# axiom_beta_interface_dummy_v0_8_540d2087.net
KiCad netlist of a schematic drawn in EAGLE
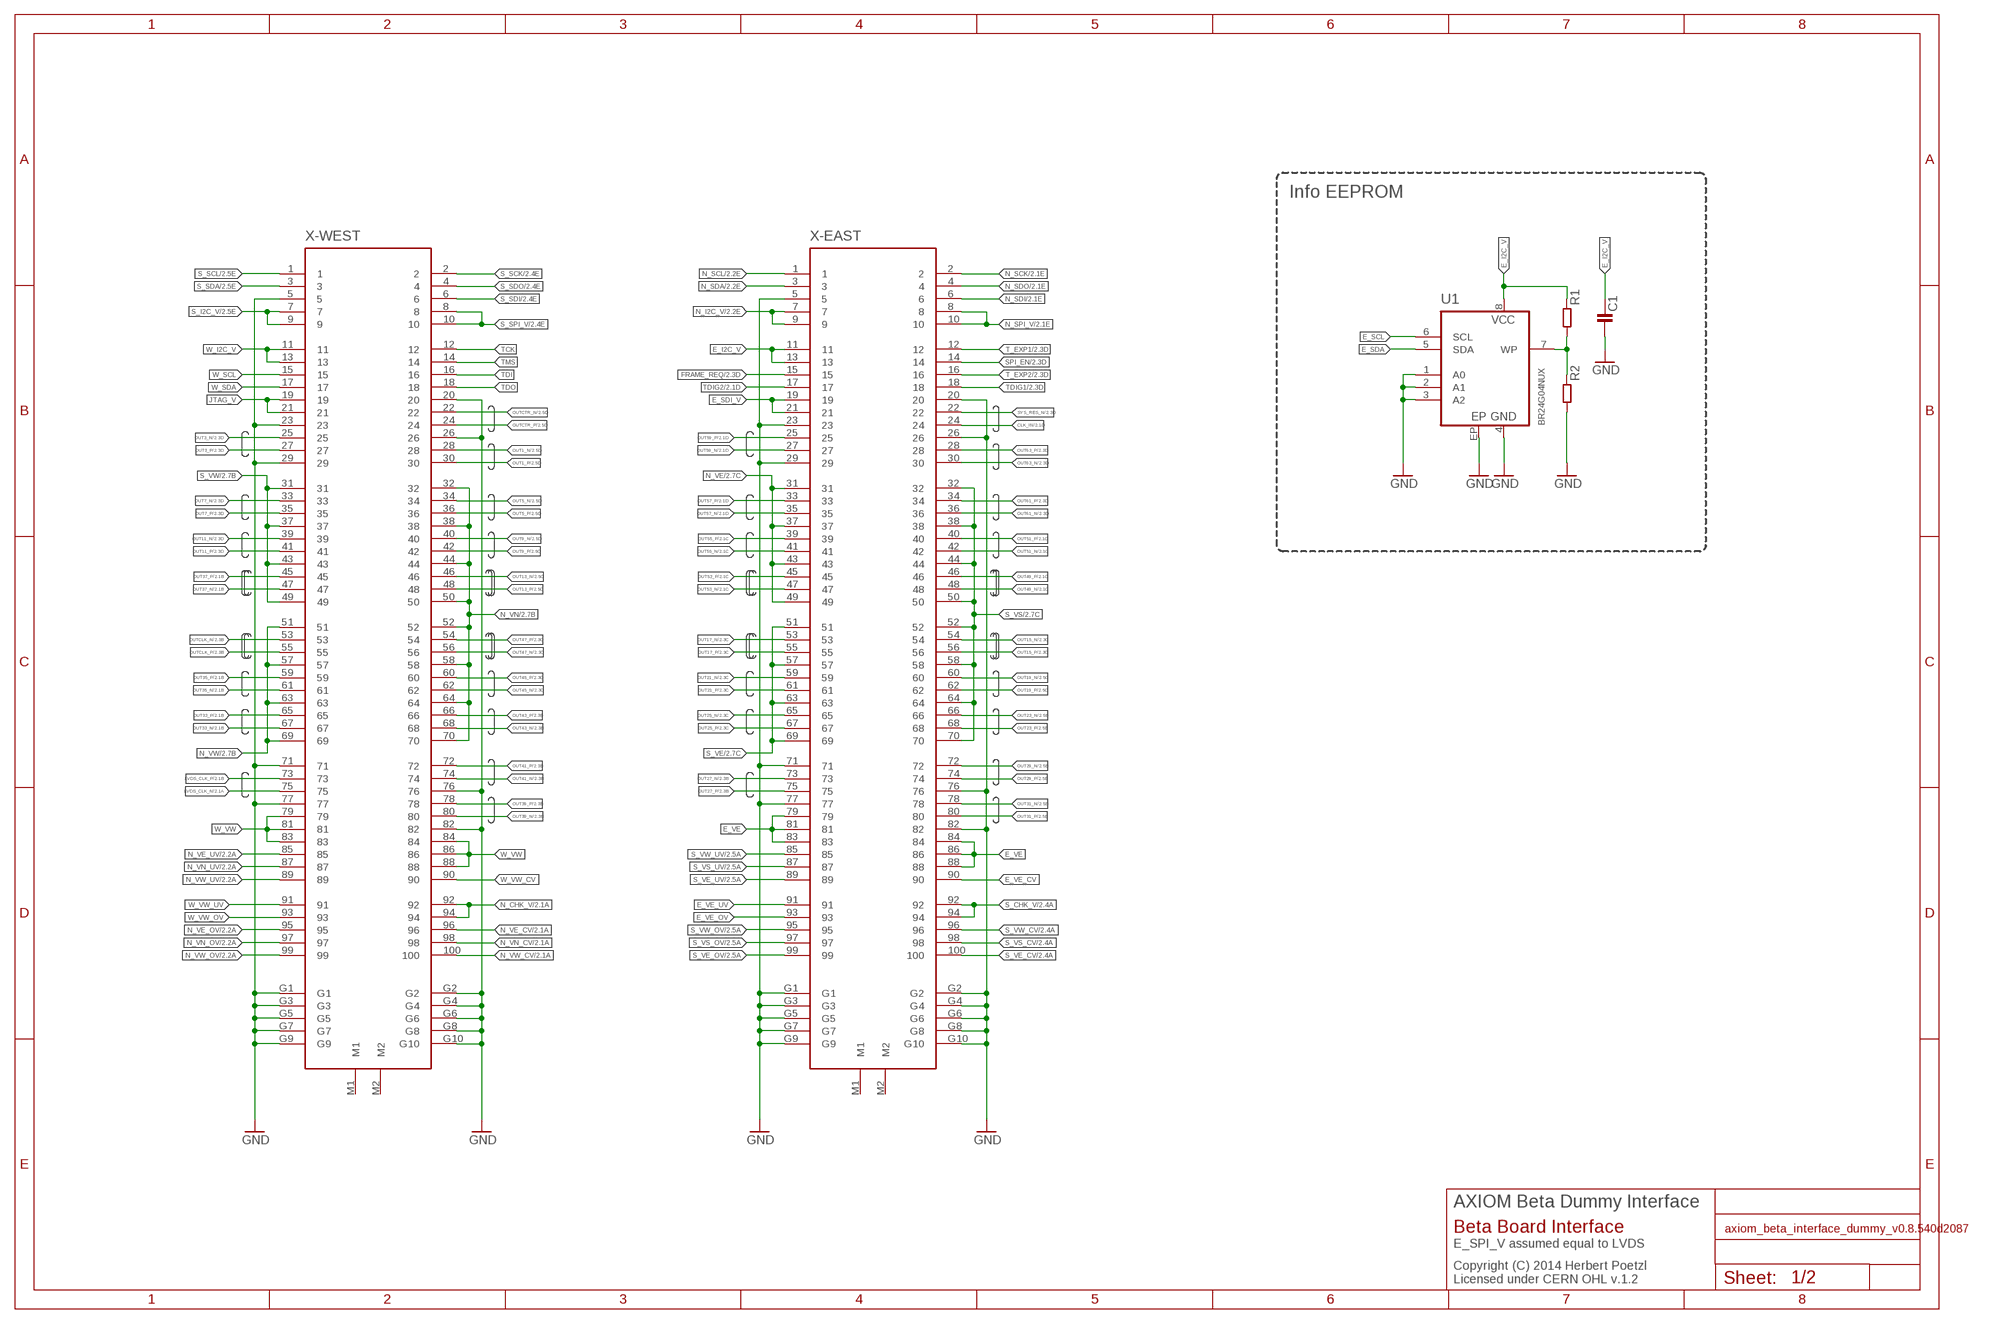
[diagram p0: schematic, sheet 1]
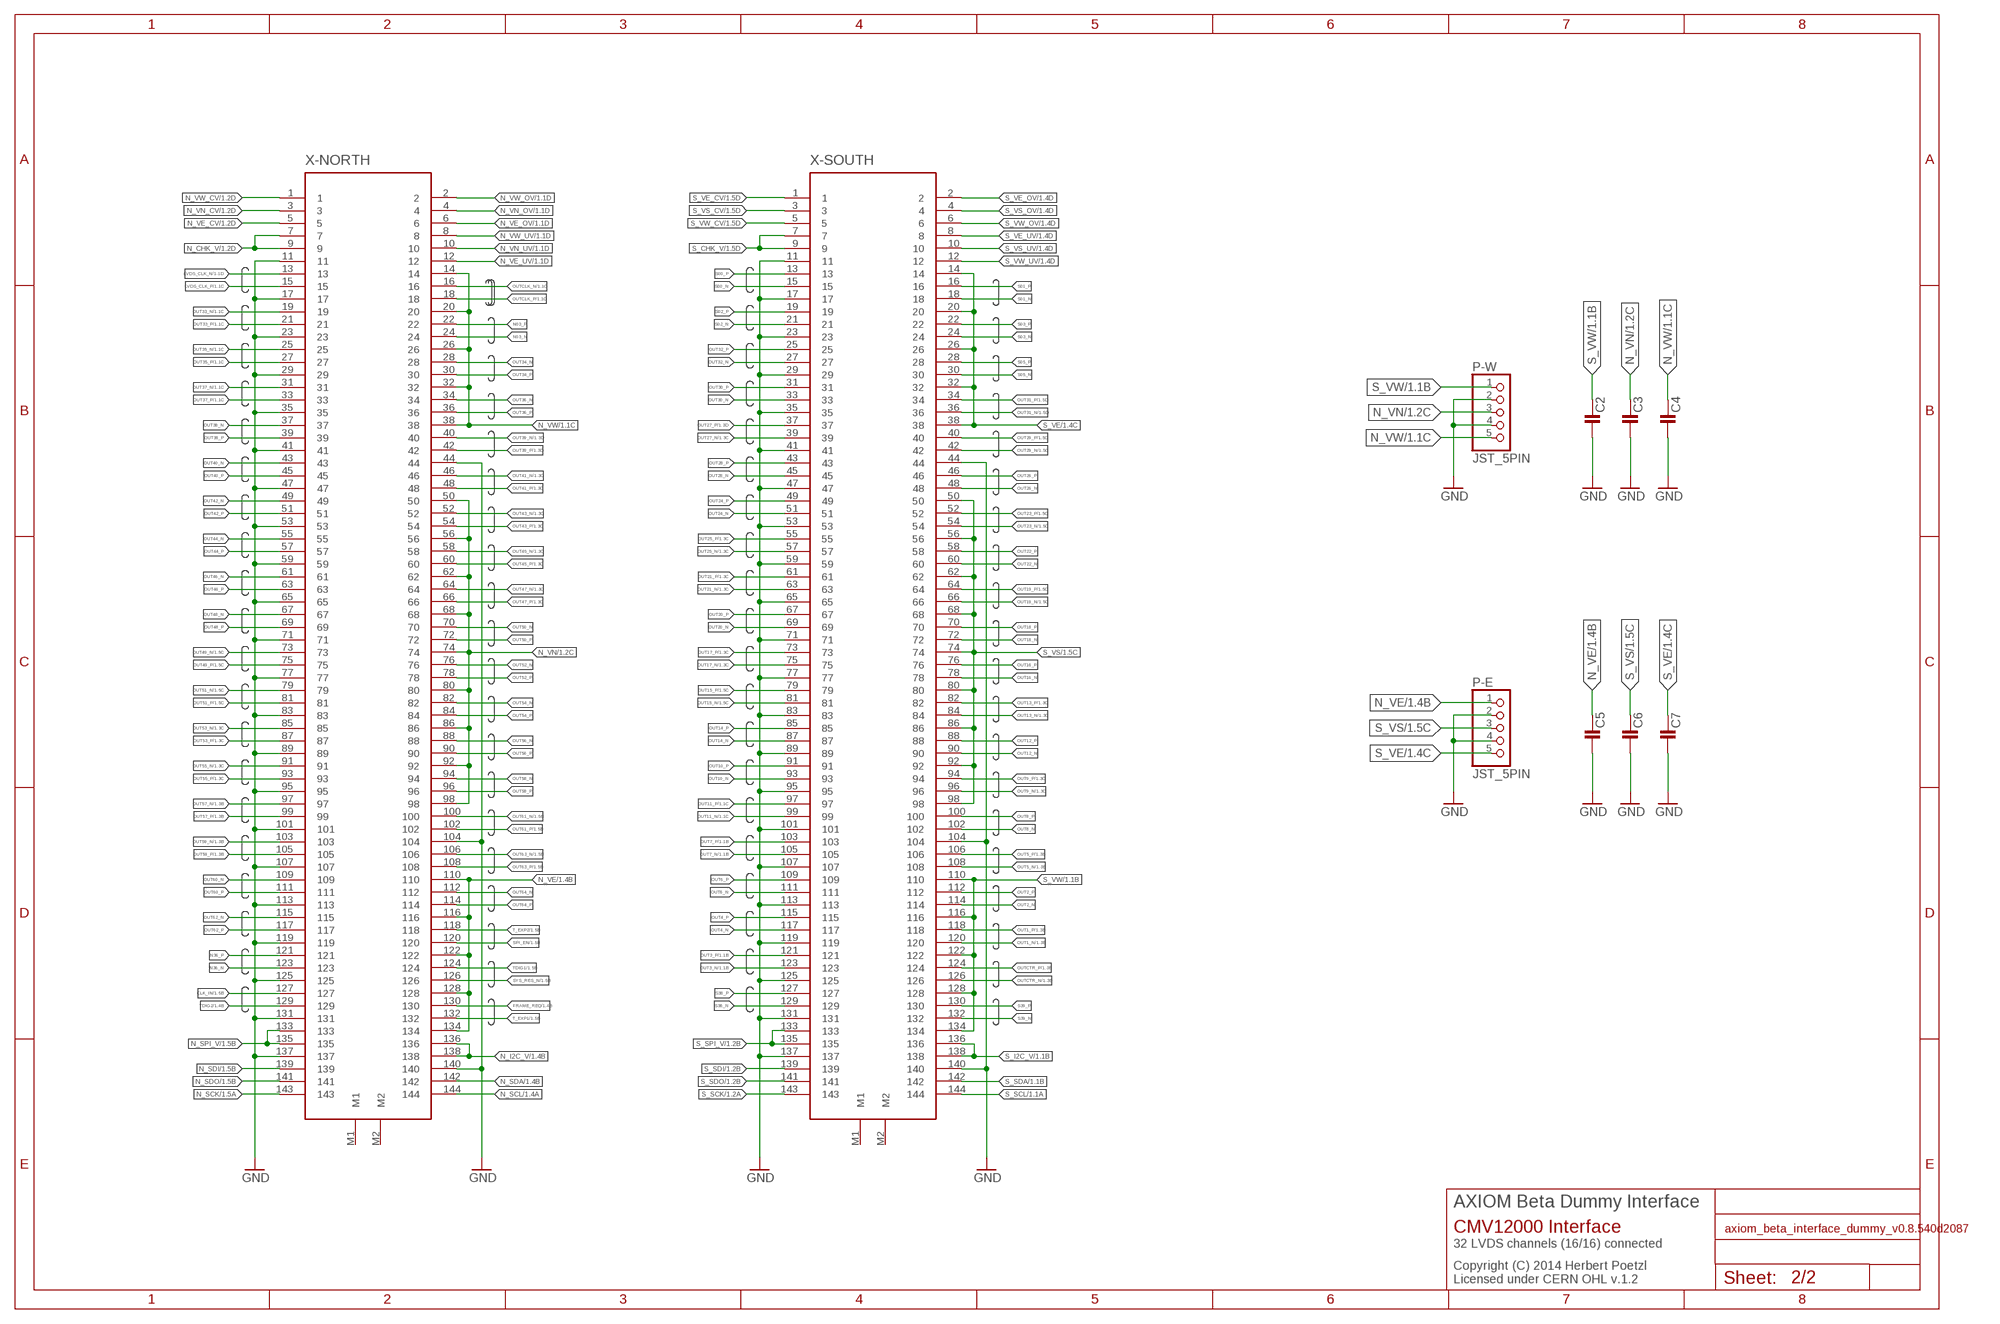
[diagram p1: schematic, sheet 2]

(export (version "E")
  (design (tool "Eeschema 10.0.6"))
  (components
    (comp (ref "C2")
      (value "C1206-B")
      (footprint "eagle-import:1206-B")
      (libsource (lib "eagle-import") (part "C1206-B"))
    )
    (comp (ref "C3")
      (value "C1206-B")
      (footprint "eagle-import:1206-B")
      (libsource (lib "eagle-import") (part "C1206-B"))
    )
    (comp (ref "C4")
      (value "C1206-B")
      (footprint "eagle-import:1206-B")
      (libsource (lib "eagle-import") (part "C1206-B"))
    )
    (comp (ref "C5")
      (value "C1206-B")
      (footprint "eagle-import:1206-B")
      (libsource (lib "eagle-import") (part "C1206-B"))
    )
    (comp (ref "C6")
      (value "C1206-B")
      (footprint "eagle-import:1206-B")
      (libsource (lib "eagle-import") (part "C1206-B"))
    )
    (comp (ref "C7")
      (value "C1206-B")
      (footprint "eagle-import:1206-B")
      (libsource (lib "eagle-import") (part "C1206-B"))
    )
    (comp (ref "P-E")
      (value "JST_5PIN")
      (footprint "eagle-import:JST-PH-5-SMT-RA")
      (libsource (lib "eagle-import") (part "JST_5PIN"))
    )
    (comp (ref "P-W")
      (value "JST_5PIN")
      (footprint "eagle-import:JST-PH-5-SMT-RA")
      (libsource (lib "eagle-import") (part "JST_5PIN"))
    )
    (comp (ref "X-NORTH")
      (value "FX10-144S")
      (footprint "eagle-import:FX10A-144S")
      (libsource (lib "eagle-import") (part "FX10-144S"))
    )
    (comp (ref "X-SOUTH")
      (value "FX10-144S")
      (footprint "eagle-import:FX10A-144S")
      (libsource (lib "eagle-import") (part "FX10-144S"))
    )
    (comp (ref "C1")
      (value "C0402-B")
      (footprint "eagle-import:0402-B")
      (libsource (lib "eagle-import") (part "C0402-B"))
    )
    (comp (ref "R1")
      (value "R0402-B")
      (footprint "eagle-import:0402-B")
      (libsource (lib "eagle-import") (part "R0402-B"))
    )
    (comp (ref "R2")
      (value "R0402-B")
      (footprint "eagle-import:0402-B")
      (libsource (lib "eagle-import") (part "R0402-B"))
    )
    (comp (ref "U1")
      (value "BR24G04NUX")
      (footprint "eagle-import:DFN200X300X100-9N")
      (libsource (lib "eagle-import") (part "BR24G04NUX"))
    )
    (comp (ref "X-EAST")
      (value "FX10-100/10P")
      (footprint "eagle-import:FX10A-100P_10")
      (libsource (lib "eagle-import") (part "FX10-100/10P"))
    )
    (comp (ref "X-WEST")
      (value "FX10-100/10P")
      (footprint "eagle-import:FX10A-100P_10")
      (libsource (lib "eagle-import") (part "FX10-100/10P"))
    )
  )
  (nets
    (net (code "1") (name "CLK_IN") (class "Default")
      (node (ref "X-EAST") (pin "24") (pinfunction "24_24") (pintype "bidirectional"))
      (node (ref "X-NORTH") (pin "127") (pinfunction "127_127") (pintype "bidirectional"))
    )
    (net (code "2") (name "E_I2C_V") (class "Default")
      (node (ref "C1") (pin "1") (pinfunction "1_1") (pintype "passive"))
      (node (ref "R1") (pin "1") (pinfunction "1_1") (pintype "passive"))
      (node (ref "U1") (pin "8") (pinfunction "VCC_8") (pintype "power_in"))
      (node (ref "X-EAST") (pin "11") (pinfunction "11_11") (pintype "bidirectional"))
      (node (ref "X-EAST") (pin "13") (pinfunction "13_13") (pintype "bidirectional"))
    )
    (net (code "3") (name "E_SCL") (class "Default")
      (node (ref "U1") (pin "6") (pinfunction "SCL_6") (pintype "input"))
    )
    (net (code "4") (name "E_SDA") (class "Default")
      (node (ref "U1") (pin "5") (pinfunction "SDA_5") (pintype "bidirectional"))
    )
    (net (code "5") (name "E_SDI_V") (class "Default")
      (node (ref "X-EAST") (pin "19") (pinfunction "19_19") (pintype "bidirectional"))
      (node (ref "X-EAST") (pin "21") (pinfunction "21_21") (pintype "bidirectional"))
    )
    (net (code "6") (name "E_VE") (class "Default")
      (node (ref "X-EAST") (pin "79") (pinfunction "79_79") (pintype "bidirectional"))
      (node (ref "X-EAST") (pin "81") (pinfunction "81_81") (pintype "bidirectional"))
      (node (ref "X-EAST") (pin "83") (pinfunction "83_83") (pintype "bidirectional"))
      (node (ref "X-EAST") (pin "84") (pinfunction "84_84") (pintype "bidirectional"))
      (node (ref "X-EAST") (pin "86") (pinfunction "86_86") (pintype "bidirectional"))
      (node (ref "X-EAST") (pin "88") (pinfunction "88_88") (pintype "bidirectional"))
    )
    (net (code "7") (name "E_VE_CV") (class "Default")
      (node (ref "X-EAST") (pin "90") (pinfunction "90_90") (pintype "bidirectional"))
    )
    (net (code "8") (name "E_VE_OV") (class "Default")
      (node (ref "X-EAST") (pin "93") (pinfunction "93_93") (pintype "bidirectional"))
    )
    (net (code "9") (name "E_VE_UV") (class "Default")
      (node (ref "X-EAST") (pin "91") (pinfunction "91_91") (pintype "bidirectional"))
    )
    (net (code "10") (name "FRAME_REQ") (class "Default")
      (node (ref "X-EAST") (pin "15") (pinfunction "15_15") (pintype "bidirectional"))
      (node (ref "X-NORTH") (pin "130") (pinfunction "130_130") (pintype "bidirectional"))
    )
    (net (code "11") (name "GND") (class "Default")
      (node (ref "C1") (pin "2") (pinfunction "2_2") (pintype "passive"))
      (node (ref "C2") (pin "2") (pinfunction "2_2") (pintype "passive"))
      (node (ref "C3") (pin "2") (pinfunction "2_2") (pintype "passive"))
      (node (ref "C4") (pin "2") (pinfunction "2_2") (pintype "passive"))
      (node (ref "C5") (pin "2") (pinfunction "2_2") (pintype "passive"))
      (node (ref "C6") (pin "2") (pinfunction "2_2") (pintype "passive"))
      (node (ref "C7") (pin "2") (pinfunction "2_2") (pintype "passive"))
      (node (ref "P-E") (pin "2") (pinfunction "2_2") (pintype "passive"))
      (node (ref "P-E") (pin "4") (pinfunction "4_4") (pintype "passive"))
      (node (ref "P-W") (pin "2") (pinfunction "2_2") (pintype "passive"))
      (node (ref "P-W") (pin "4") (pinfunction "4_4") (pintype "passive"))
      (node (ref "R2") (pin "2") (pinfunction "2_2") (pintype "passive"))
      (node (ref "U1") (pin "1") (pinfunction "A0_1") (pintype "input"))
      (node (ref "U1") (pin "2") (pinfunction "A1_2") (pintype "input"))
      (node (ref "U1") (pin "3") (pinfunction "A2_3") (pintype "input"))
      (node (ref "U1") (pin "4") (pinfunction "GND_4") (pintype "passive"))
      (node (ref "U1") (pin "EP") (pinfunction "EP_EP") (pintype "passive"))
      (node (ref "X-EAST") (pin "20") (pinfunction "20_20") (pintype "bidirectional"))
      (node (ref "X-EAST") (pin "23") (pinfunction "23_23") (pintype "bidirectional"))
      (node (ref "X-EAST") (pin "26") (pinfunction "26_26") (pintype "bidirectional"))
      (node (ref "X-EAST") (pin "29") (pinfunction "29_29") (pintype "bidirectional"))
      (node (ref "X-EAST") (pin "5") (pinfunction "5_5") (pintype "bidirectional"))
      (node (ref "X-EAST") (pin "71") (pinfunction "71_71") (pintype "bidirectional"))
      (node (ref "X-EAST") (pin "76") (pinfunction "76_76") (pintype "bidirectional"))
      (node (ref "X-EAST") (pin "77") (pinfunction "77_77") (pintype "bidirectional"))
      (node (ref "X-EAST") (pin "82") (pinfunction "82_82") (pintype "bidirectional"))
      (node (ref "X-EAST") (pin "G1") (pinfunction "G1_G1") (pintype "bidirectional"))
      (node (ref "X-EAST") (pin "G10") (pinfunction "G10_G10") (pintype "bidirectional"))
      (node (ref "X-EAST") (pin "G2") (pinfunction "G2_G2") (pintype "bidirectional"))
      (node (ref "X-EAST") (pin "G3") (pinfunction "G3_G3") (pintype "bidirectional"))
      (node (ref "X-EAST") (pin "G4") (pinfunction "G4_G4") (pintype "bidirectional"))
      (node (ref "X-EAST") (pin "G5") (pinfunction "G5_G5") (pintype "bidirectional"))
      (node (ref "X-EAST") (pin "G6") (pinfunction "G6_G6") (pintype "bidirectional"))
      (node (ref "X-EAST") (pin "G7") (pinfunction "G7_G7") (pintype "bidirectional"))
      (node (ref "X-EAST") (pin "G8") (pinfunction "G8_G8") (pintype "bidirectional"))
      (node (ref "X-EAST") (pin "G9") (pinfunction "G9_G9") (pintype "bidirectional"))
      (node (ref "X-NORTH") (pin "101") (pinfunction "101_101") (pintype "bidirectional"))
      (node (ref "X-NORTH") (pin "104") (pinfunction "104_104") (pintype "bidirectional"))
      (node (ref "X-NORTH") (pin "107") (pinfunction "107_107") (pintype "bidirectional"))
      (node (ref "X-NORTH") (pin "11") (pinfunction "11_11") (pintype "bidirectional"))
      (node (ref "X-NORTH") (pin "113") (pinfunction "113_113") (pintype "bidirectional"))
      (node (ref "X-NORTH") (pin "119") (pinfunction "119_119") (pintype "bidirectional"))
      (node (ref "X-NORTH") (pin "125") (pinfunction "125_125") (pintype "bidirectional"))
      (node (ref "X-NORTH") (pin "131") (pinfunction "131_131") (pintype "bidirectional"))
      (node (ref "X-NORTH") (pin "137") (pinfunction "137_137") (pintype "bidirectional"))
      (node (ref "X-NORTH") (pin "140") (pinfunction "140_140") (pintype "bidirectional"))
      (node (ref "X-NORTH") (pin "17") (pinfunction "17_17") (pintype "bidirectional"))
      (node (ref "X-NORTH") (pin "23") (pinfunction "23_23") (pintype "bidirectional"))
      (node (ref "X-NORTH") (pin "29") (pinfunction "29_29") (pintype "bidirectional"))
      (node (ref "X-NORTH") (pin "35") (pinfunction "35_35") (pintype "bidirectional"))
      (node (ref "X-NORTH") (pin "41") (pinfunction "41_41") (pintype "bidirectional"))
      (node (ref "X-NORTH") (pin "44") (pinfunction "44_44") (pintype "bidirectional"))
      (node (ref "X-NORTH") (pin "47") (pinfunction "47_47") (pintype "bidirectional"))
      (node (ref "X-NORTH") (pin "53") (pinfunction "53_53") (pintype "bidirectional"))
      (node (ref "X-NORTH") (pin "59") (pinfunction "59_59") (pintype "bidirectional"))
      (node (ref "X-NORTH") (pin "65") (pinfunction "65_65") (pintype "bidirectional"))
      (node (ref "X-NORTH") (pin "71") (pinfunction "71_71") (pintype "bidirectional"))
      (node (ref "X-NORTH") (pin "77") (pinfunction "77_77") (pintype "bidirectional"))
      (node (ref "X-NORTH") (pin "83") (pinfunction "83_83") (pintype "bidirectional"))
      (node (ref "X-NORTH") (pin "89") (pinfunction "89_89") (pintype "bidirectional"))
      (node (ref "X-NORTH") (pin "95") (pinfunction "95_95") (pintype "bidirectional"))
      (node (ref "X-SOUTH") (pin "101") (pinfunction "101_101") (pintype "bidirectional"))
      (node (ref "X-SOUTH") (pin "104") (pinfunction "104_104") (pintype "bidirectional"))
      (node (ref "X-SOUTH") (pin "107") (pinfunction "107_107") (pintype "bidirectional"))
      (node (ref "X-SOUTH") (pin "11") (pinfunction "11_11") (pintype "bidirectional"))
      (node (ref "X-SOUTH") (pin "113") (pinfunction "113_113") (pintype "bidirectional"))
      (node (ref "X-SOUTH") (pin "119") (pinfunction "119_119") (pintype "bidirectional"))
      (node (ref "X-SOUTH") (pin "125") (pinfunction "125_125") (pintype "bidirectional"))
      (node (ref "X-SOUTH") (pin "131") (pinfunction "131_131") (pintype "bidirectional"))
      (node (ref "X-SOUTH") (pin "137") (pinfunction "137_137") (pintype "bidirectional"))
      (node (ref "X-SOUTH") (pin "140") (pinfunction "140_140") (pintype "bidirectional"))
      (node (ref "X-SOUTH") (pin "17") (pinfunction "17_17") (pintype "bidirectional"))
      (node (ref "X-SOUTH") (pin "23") (pinfunction "23_23") (pintype "bidirectional"))
      (node (ref "X-SOUTH") (pin "29") (pinfunction "29_29") (pintype "bidirectional"))
      (node (ref "X-SOUTH") (pin "35") (pinfunction "35_35") (pintype "bidirectional"))
      (node (ref "X-SOUTH") (pin "41") (pinfunction "41_41") (pintype "bidirectional"))
      (node (ref "X-SOUTH") (pin "44") (pinfunction "44_44") (pintype "bidirectional"))
      (node (ref "X-SOUTH") (pin "47") (pinfunction "47_47") (pintype "bidirectional"))
      (node (ref "X-SOUTH") (pin "53") (pinfunction "53_53") (pintype "bidirectional"))
      (node (ref "X-SOUTH") (pin "59") (pinfunction "59_59") (pintype "bidirectional"))
      (node (ref "X-SOUTH") (pin "65") (pinfunction "65_65") (pintype "bidirectional"))
      (node (ref "X-SOUTH") (pin "71") (pinfunction "71_71") (pintype "bidirectional"))
      (node (ref "X-SOUTH") (pin "77") (pinfunction "77_77") (pintype "bidirectional"))
      (node (ref "X-SOUTH") (pin "83") (pinfunction "83_83") (pintype "bidirectional"))
      (node (ref "X-SOUTH") (pin "89") (pinfunction "89_89") (pintype "bidirectional"))
      (node (ref "X-SOUTH") (pin "95") (pinfunction "95_95") (pintype "bidirectional"))
      (node (ref "X-WEST") (pin "20") (pinfunction "20_20") (pintype "bidirectional"))
      (node (ref "X-WEST") (pin "23") (pinfunction "23_23") (pintype "bidirectional"))
      (node (ref "X-WEST") (pin "26") (pinfunction "26_26") (pintype "bidirectional"))
      (node (ref "X-WEST") (pin "29") (pinfunction "29_29") (pintype "bidirectional"))
      (node (ref "X-WEST") (pin "5") (pinfunction "5_5") (pintype "bidirectional"))
      (node (ref "X-WEST") (pin "71") (pinfunction "71_71") (pintype "bidirectional"))
      (node (ref "X-WEST") (pin "76") (pinfunction "76_76") (pintype "bidirectional"))
      (node (ref "X-WEST") (pin "77") (pinfunction "77_77") (pintype "bidirectional"))
      (node (ref "X-WEST") (pin "82") (pinfunction "82_82") (pintype "bidirectional"))
      (node (ref "X-WEST") (pin "G1") (pinfunction "G1_G1") (pintype "bidirectional"))
      (node (ref "X-WEST") (pin "G10") (pinfunction "G10_G10") (pintype "bidirectional"))
      (node (ref "X-WEST") (pin "G2") (pinfunction "G2_G2") (pintype "bidirectional"))
      (node (ref "X-WEST") (pin "G3") (pinfunction "G3_G3") (pintype "bidirectional"))
      (node (ref "X-WEST") (pin "G4") (pinfunction "G4_G4") (pintype "bidirectional"))
      (node (ref "X-WEST") (pin "G5") (pinfunction "G5_G5") (pintype "bidirectional"))
      (node (ref "X-WEST") (pin "G6") (pinfunction "G6_G6") (pintype "bidirectional"))
      (node (ref "X-WEST") (pin "G7") (pinfunction "G7_G7") (pintype "bidirectional"))
      (node (ref "X-WEST") (pin "G8") (pinfunction "G8_G8") (pintype "bidirectional"))
      (node (ref "X-WEST") (pin "G9") (pinfunction "G9_G9") (pintype "bidirectional"))
    )
    (net (code "12") (name "JTAG_V") (class "Default")
      (node (ref "X-WEST") (pin "19") (pinfunction "19_19") (pintype "bidirectional"))
      (node (ref "X-WEST") (pin "21") (pinfunction "21_21") (pintype "bidirectional"))
    )
    (net (code "13") (name "LVDS_CLK_N") (class "Default")
      (node (ref "X-NORTH") (pin "13") (pinfunction "13_13") (pintype "bidirectional"))
      (node (ref "X-WEST") (pin "75") (pinfunction "75_75") (pintype "bidirectional"))
    )
    (net (code "14") (name "LVDS_CLK_P") (class "Default")
      (node (ref "X-NORTH") (pin "15") (pinfunction "15_15") (pintype "bidirectional"))
      (node (ref "X-WEST") (pin "73") (pinfunction "73_73") (pintype "bidirectional"))
    )
    (net (code "15") (name "N03_N") (class "Default")
      (node (ref "X-NORTH") (pin "24") (pinfunction "24_24") (pintype "bidirectional"))
    )
    (net (code "16") (name "N03_P") (class "Default")
      (node (ref "X-NORTH") (pin "22") (pinfunction "22_22") (pintype "bidirectional"))
    )
    (net (code "17") (name "N36_N") (class "Default")
      (node (ref "X-NORTH") (pin "123") (pinfunction "123_123") (pintype "bidirectional"))
    )
    (net (code "18") (name "N36_P") (class "Default")
      (node (ref "X-NORTH") (pin "121") (pinfunction "121_121") (pintype "bidirectional"))
    )
    (net (code "19") (name "N_CHK_V") (class "Default")
      (node (ref "X-NORTH") (pin "7") (pinfunction "7_7") (pintype "bidirectional"))
      (node (ref "X-NORTH") (pin "9") (pinfunction "9_9") (pintype "bidirectional"))
      (node (ref "X-WEST") (pin "92") (pinfunction "92_92") (pintype "bidirectional"))
      (node (ref "X-WEST") (pin "94") (pinfunction "94_94") (pintype "bidirectional"))
    )
    (net (code "20") (name "N_I2C_V") (class "Default")
      (node (ref "X-EAST") (pin "7") (pinfunction "7_7") (pintype "bidirectional"))
      (node (ref "X-EAST") (pin "9") (pinfunction "9_9") (pintype "bidirectional"))
      (node (ref "X-NORTH") (pin "136") (pinfunction "136_136") (pintype "bidirectional"))
      (node (ref "X-NORTH") (pin "138") (pinfunction "138_138") (pintype "bidirectional"))
    )
    (net (code "21") (name "N_SCK") (class "Default")
      (node (ref "X-EAST") (pin "2") (pinfunction "2_2") (pintype "bidirectional"))
      (node (ref "X-NORTH") (pin "143") (pinfunction "143_143") (pintype "bidirectional"))
    )
    (net (code "22") (name "N_SCL") (class "Default")
      (node (ref "X-EAST") (pin "1") (pinfunction "1_1") (pintype "bidirectional"))
      (node (ref "X-NORTH") (pin "144") (pinfunction "144_144") (pintype "bidirectional"))
    )
    (net (code "23") (name "N_SDA") (class "Default")
      (node (ref "X-EAST") (pin "3") (pinfunction "3_3") (pintype "bidirectional"))
      (node (ref "X-NORTH") (pin "142") (pinfunction "142_142") (pintype "bidirectional"))
    )
    (net (code "24") (name "N_SDI") (class "Default")
      (node (ref "X-EAST") (pin "6") (pinfunction "6_6") (pintype "bidirectional"))
      (node (ref "X-NORTH") (pin "139") (pinfunction "139_139") (pintype "bidirectional"))
    )
    (net (code "25") (name "N_SDO") (class "Default")
      (node (ref "X-EAST") (pin "4") (pinfunction "4_4") (pintype "bidirectional"))
      (node (ref "X-NORTH") (pin "141") (pinfunction "141_141") (pintype "bidirectional"))
    )
    (net (code "26") (name "N_SPI_V") (class "Default")
      (node (ref "X-EAST") (pin "10") (pinfunction "10_10") (pintype "bidirectional"))
      (node (ref "X-EAST") (pin "8") (pinfunction "8_8") (pintype "bidirectional"))
      (node (ref "X-NORTH") (pin "133") (pinfunction "133_133") (pintype "bidirectional"))
      (node (ref "X-NORTH") (pin "135") (pinfunction "135_135") (pintype "bidirectional"))
    )
    (net (code "27") (name "N_VE") (class "Default")
      (node (ref "C5") (pin "1") (pinfunction "1_1") (pintype "passive"))
      (node (ref "P-E") (pin "1") (pinfunction "1_1") (pintype "passive"))
      (node (ref "X-EAST") (pin "31") (pinfunction "31_31") (pintype "bidirectional"))
      (node (ref "X-EAST") (pin "37") (pinfunction "37_37") (pintype "bidirectional"))
      (node (ref "X-EAST") (pin "43") (pinfunction "43_43") (pintype "bidirectional"))
      (node (ref "X-EAST") (pin "49") (pinfunction "49_49") (pintype "bidirectional"))
      (node (ref "X-NORTH") (pin "110") (pinfunction "110_110") (pintype "bidirectional"))
      (node (ref "X-NORTH") (pin "116") (pinfunction "116_116") (pintype "bidirectional"))
      (node (ref "X-NORTH") (pin "122") (pinfunction "122_122") (pintype "bidirectional"))
      (node (ref "X-NORTH") (pin "128") (pinfunction "128_128") (pintype "bidirectional"))
      (node (ref "X-NORTH") (pin "134") (pinfunction "134_134") (pintype "bidirectional"))
    )
    (net (code "28") (name "N_VE_CV") (class "Default")
      (node (ref "X-NORTH") (pin "5") (pinfunction "5_5") (pintype "bidirectional"))
      (node (ref "X-WEST") (pin "96") (pinfunction "96_96") (pintype "bidirectional"))
    )
    (net (code "29") (name "N_VE_OV") (class "Default")
      (node (ref "X-NORTH") (pin "6") (pinfunction "6_6") (pintype "bidirectional"))
      (node (ref "X-WEST") (pin "95") (pinfunction "95_95") (pintype "bidirectional"))
    )
    (net (code "30") (name "N_VE_UV") (class "Default")
      (node (ref "X-NORTH") (pin "12") (pinfunction "12_12") (pintype "bidirectional"))
      (node (ref "X-WEST") (pin "85") (pinfunction "85_85") (pintype "bidirectional"))
    )
    (net (code "31") (name "N_VN") (class "Default")
      (node (ref "C3") (pin "1") (pinfunction "1_1") (pintype "passive"))
      (node (ref "P-W") (pin "3") (pinfunction "3_3") (pintype "passive"))
      (node (ref "X-NORTH") (pin "50") (pinfunction "50_50") (pintype "bidirectional"))
      (node (ref "X-NORTH") (pin "56") (pinfunction "56_56") (pintype "bidirectional"))
      (node (ref "X-NORTH") (pin "62") (pinfunction "62_62") (pintype "bidirectional"))
      (node (ref "X-NORTH") (pin "68") (pinfunction "68_68") (pintype "bidirectional"))
      (node (ref "X-NORTH") (pin "74") (pinfunction "74_74") (pintype "bidirectional"))
      (node (ref "X-NORTH") (pin "80") (pinfunction "80_80") (pintype "bidirectional"))
      (node (ref "X-NORTH") (pin "86") (pinfunction "86_86") (pintype "bidirectional"))
      (node (ref "X-NORTH") (pin "92") (pinfunction "92_92") (pintype "bidirectional"))
      (node (ref "X-NORTH") (pin "98") (pinfunction "98_98") (pintype "bidirectional"))
      (node (ref "X-WEST") (pin "32") (pinfunction "32_32") (pintype "bidirectional"))
      (node (ref "X-WEST") (pin "38") (pinfunction "38_38") (pintype "bidirectional"))
      (node (ref "X-WEST") (pin "44") (pinfunction "44_44") (pintype "bidirectional"))
      (node (ref "X-WEST") (pin "50") (pinfunction "50_50") (pintype "bidirectional"))
      (node (ref "X-WEST") (pin "52") (pinfunction "52_52") (pintype "bidirectional"))
      (node (ref "X-WEST") (pin "58") (pinfunction "58_58") (pintype "bidirectional"))
      (node (ref "X-WEST") (pin "64") (pinfunction "64_64") (pintype "bidirectional"))
      (node (ref "X-WEST") (pin "70") (pinfunction "70_70") (pintype "bidirectional"))
    )
    (net (code "32") (name "N_VN_CV") (class "Default")
      (node (ref "X-NORTH") (pin "3") (pinfunction "3_3") (pintype "bidirectional"))
      (node (ref "X-WEST") (pin "98") (pinfunction "98_98") (pintype "bidirectional"))
    )
    (net (code "33") (name "N_VN_OV") (class "Default")
      (node (ref "X-NORTH") (pin "4") (pinfunction "4_4") (pintype "bidirectional"))
      (node (ref "X-WEST") (pin "97") (pinfunction "97_97") (pintype "bidirectional"))
    )
    (net (code "34") (name "N_VN_UV") (class "Default")
      (node (ref "X-NORTH") (pin "10") (pinfunction "10_10") (pintype "bidirectional"))
      (node (ref "X-WEST") (pin "87") (pinfunction "87_87") (pintype "bidirectional"))
    )
    (net (code "35") (name "N_VW") (class "Default")
      (node (ref "C4") (pin "1") (pinfunction "1_1") (pintype "passive"))
      (node (ref "P-W") (pin "5") (pinfunction "5_5") (pintype "passive"))
      (node (ref "X-NORTH") (pin "14") (pinfunction "14_14") (pintype "bidirectional"))
      (node (ref "X-NORTH") (pin "20") (pinfunction "20_20") (pintype "bidirectional"))
      (node (ref "X-NORTH") (pin "26") (pinfunction "26_26") (pintype "bidirectional"))
      (node (ref "X-NORTH") (pin "32") (pinfunction "32_32") (pintype "bidirectional"))
      (node (ref "X-NORTH") (pin "38") (pinfunction "38_38") (pintype "bidirectional"))
      (node (ref "X-WEST") (pin "51") (pinfunction "51_51") (pintype "bidirectional"))
      (node (ref "X-WEST") (pin "57") (pinfunction "57_57") (pintype "bidirectional"))
      (node (ref "X-WEST") (pin "63") (pinfunction "63_63") (pintype "bidirectional"))
      (node (ref "X-WEST") (pin "69") (pinfunction "69_69") (pintype "bidirectional"))
    )
    (net (code "36") (name "N_VW_CV") (class "Default")
      (node (ref "X-NORTH") (pin "1") (pinfunction "1_1") (pintype "bidirectional"))
      (node (ref "X-WEST") (pin "100") (pinfunction "100_100") (pintype "bidirectional"))
    )
    (net (code "37") (name "N_VW_OV") (class "Default")
      (node (ref "X-NORTH") (pin "2") (pinfunction "2_2") (pintype "bidirectional"))
      (node (ref "X-WEST") (pin "99") (pinfunction "99_99") (pintype "bidirectional"))
    )
    (net (code "38") (name "N_VW_UV") (class "Default")
      (node (ref "X-NORTH") (pin "8") (pinfunction "8_8") (pintype "bidirectional"))
      (node (ref "X-WEST") (pin "89") (pinfunction "89_89") (pintype "bidirectional"))
    )
    (net (code "39") (name "Net-(U1-WP)") (class "Default")
      (node (ref "R1") (pin "2") (pinfunction "2_2") (pintype "passive"))
      (node (ref "R2") (pin "1") (pinfunction "1_1") (pintype "passive"))
      (node (ref "U1") (pin "7") (pinfunction "WP_7") (pintype "input"))
    )
    (net (code "40") (name "OUT1_N") (class "Default")
      (node (ref "X-SOUTH") (pin "120") (pinfunction "120_120") (pintype "bidirectional"))
      (node (ref "X-WEST") (pin "28") (pinfunction "28_28") (pintype "bidirectional"))
    )
    (net (code "41") (name "OUT1_P") (class "Default")
      (node (ref "X-SOUTH") (pin "118") (pinfunction "118_118") (pintype "bidirectional"))
      (node (ref "X-WEST") (pin "30") (pinfunction "30_30") (pintype "bidirectional"))
    )
    (net (code "42") (name "OUT2_N") (class "Default")
      (node (ref "X-SOUTH") (pin "114") (pinfunction "114_114") (pintype "bidirectional"))
    )
    (net (code "43") (name "OUT2_P") (class "Default")
      (node (ref "X-SOUTH") (pin "112") (pinfunction "112_112") (pintype "bidirectional"))
    )
    (net (code "44") (name "OUT3_N") (class "Default")
      (node (ref "X-SOUTH") (pin "123") (pinfunction "123_123") (pintype "bidirectional"))
      (node (ref "X-WEST") (pin "25") (pinfunction "25_25") (pintype "bidirectional"))
    )
    (net (code "45") (name "OUT3_P") (class "Default")
      (node (ref "X-SOUTH") (pin "121") (pinfunction "121_121") (pintype "bidirectional"))
      (node (ref "X-WEST") (pin "27") (pinfunction "27_27") (pintype "bidirectional"))
    )
    (net (code "46") (name "OUT4_N") (class "Default")
      (node (ref "X-SOUTH") (pin "117") (pinfunction "117_117") (pintype "bidirectional"))
    )
    (net (code "47") (name "OUT4_P") (class "Default")
      (node (ref "X-SOUTH") (pin "115") (pinfunction "115_115") (pintype "bidirectional"))
    )
    (net (code "48") (name "OUT5_N") (class "Default")
      (node (ref "X-SOUTH") (pin "108") (pinfunction "108_108") (pintype "bidirectional"))
      (node (ref "X-WEST") (pin "34") (pinfunction "34_34") (pintype "bidirectional"))
    )
    (net (code "49") (name "OUT5_P") (class "Default")
      (node (ref "X-SOUTH") (pin "106") (pinfunction "106_106") (pintype "bidirectional"))
      (node (ref "X-WEST") (pin "36") (pinfunction "36_36") (pintype "bidirectional"))
    )
    (net (code "50") (name "OUT6_N") (class "Default")
      (node (ref "X-SOUTH") (pin "111") (pinfunction "111_111") (pintype "bidirectional"))
    )
    (net (code "51") (name "OUT6_P") (class "Default")
      (node (ref "X-SOUTH") (pin "109") (pinfunction "109_109") (pintype "bidirectional"))
    )
    (net (code "52") (name "OUT7_N") (class "Default")
      (node (ref "X-SOUTH") (pin "105") (pinfunction "105_105") (pintype "bidirectional"))
      (node (ref "X-WEST") (pin "33") (pinfunction "33_33") (pintype "bidirectional"))
    )
    (net (code "53") (name "OUT7_P") (class "Default")
      (node (ref "X-SOUTH") (pin "103") (pinfunction "103_103") (pintype "bidirectional"))
      (node (ref "X-WEST") (pin "35") (pinfunction "35_35") (pintype "bidirectional"))
    )
    (net (code "54") (name "OUT8_N") (class "Default")
      (node (ref "X-SOUTH") (pin "102") (pinfunction "102_102") (pintype "bidirectional"))
    )
    (net (code "55") (name "OUT8_P") (class "Default")
      (node (ref "X-SOUTH") (pin "100") (pinfunction "100_100") (pintype "bidirectional"))
    )
    (net (code "56") (name "OUT9_N") (class "Default")
      (node (ref "X-SOUTH") (pin "96") (pinfunction "96_96") (pintype "bidirectional"))
      (node (ref "X-WEST") (pin "40") (pinfunction "40_40") (pintype "bidirectional"))
    )
    (net (code "57") (name "OUT9_P") (class "Default")
      (node (ref "X-SOUTH") (pin "94") (pinfunction "94_94") (pintype "bidirectional"))
      (node (ref "X-WEST") (pin "42") (pinfunction "42_42") (pintype "bidirectional"))
    )
    (net (code "58") (name "OUT10_N") (class "Default")
      (node (ref "X-SOUTH") (pin "93") (pinfunction "93_93") (pintype "bidirectional"))
    )
    (net (code "59") (name "OUT10_P") (class "Default")
      (node (ref "X-SOUTH") (pin "91") (pinfunction "91_91") (pintype "bidirectional"))
    )
    (net (code "60") (name "OUT11_N") (class "Default")
      (node (ref "X-SOUTH") (pin "99") (pinfunction "99_99") (pintype "bidirectional"))
      (node (ref "X-WEST") (pin "39") (pinfunction "39_39") (pintype "bidirectional"))
    )
    (net (code "61") (name "OUT11_P") (class "Default")
      (node (ref "X-SOUTH") (pin "97") (pinfunction "97_97") (pintype "bidirectional"))
      (node (ref "X-WEST") (pin "41") (pinfunction "41_41") (pintype "bidirectional"))
    )
    (net (code "62") (name "OUT12_N") (class "Default")
      (node (ref "X-SOUTH") (pin "90") (pinfunction "90_90") (pintype "bidirectional"))
    )
    (net (code "63") (name "OUT12_P") (class "Default")
      (node (ref "X-SOUTH") (pin "88") (pinfunction "88_88") (pintype "bidirectional"))
    )
    (net (code "64") (name "OUT13_N") (class "Default")
      (node (ref "X-SOUTH") (pin "84") (pinfunction "84_84") (pintype "bidirectional"))
      (node (ref "X-WEST") (pin "46") (pinfunction "46_46") (pintype "bidirectional"))
    )
    (net (code "65") (name "OUT13_P") (class "Default")
      (node (ref "X-SOUTH") (pin "82") (pinfunction "82_82") (pintype "bidirectional"))
      (node (ref "X-WEST") (pin "48") (pinfunction "48_48") (pintype "bidirectional"))
    )
    (net (code "66") (name "OUT14_N") (class "Default")
      (node (ref "X-SOUTH") (pin "87") (pinfunction "87_87") (pintype "bidirectional"))
    )
    (net (code "67") (name "OUT14_P") (class "Default")
      (node (ref "X-SOUTH") (pin "85") (pinfunction "85_85") (pintype "bidirectional"))
    )
    (net (code "68") (name "OUT15_N") (class "Default")
      (node (ref "X-EAST") (pin "54") (pinfunction "54_54") (pintype "bidirectional"))
      (node (ref "X-SOUTH") (pin "81") (pinfunction "81_81") (pintype "bidirectional"))
    )
    (net (code "69") (name "OUT15_P") (class "Default")
      (node (ref "X-EAST") (pin "56") (pinfunction "56_56") (pintype "bidirectional"))
      (node (ref "X-SOUTH") (pin "79") (pinfunction "79_79") (pintype "bidirectional"))
    )
    (net (code "70") (name "OUT16_N") (class "Default")
      (node (ref "X-SOUTH") (pin "78") (pinfunction "78_78") (pintype "bidirectional"))
    )
    (net (code "71") (name "OUT16_P") (class "Default")
      (node (ref "X-SOUTH") (pin "76") (pinfunction "76_76") (pintype "bidirectional"))
    )
    (net (code "72") (name "OUT17_N") (class "Default")
      (node (ref "X-EAST") (pin "53") (pinfunction "53_53") (pintype "bidirectional"))
      (node (ref "X-SOUTH") (pin "75") (pinfunction "75_75") (pintype "bidirectional"))
    )
    (net (code "73") (name "OUT17_P") (class "Default")
      (node (ref "X-EAST") (pin "55") (pinfunction "55_55") (pintype "bidirectional"))
      (node (ref "X-SOUTH") (pin "73") (pinfunction "73_73") (pintype "bidirectional"))
    )
    (net (code "74") (name "OUT18_N") (class "Default")
      (node (ref "X-SOUTH") (pin "72") (pinfunction "72_72") (pintype "bidirectional"))
    )
    (net (code "75") (name "OUT18_P") (class "Default")
      (node (ref "X-SOUTH") (pin "70") (pinfunction "70_70") (pintype "bidirectional"))
    )
    (net (code "76") (name "OUT19_N") (class "Default")
      (node (ref "X-EAST") (pin "60") (pinfunction "60_60") (pintype "bidirectional"))
      (node (ref "X-SOUTH") (pin "66") (pinfunction "66_66") (pintype "bidirectional"))
    )
    (net (code "77") (name "OUT19_P") (class "Default")
      (node (ref "X-EAST") (pin "62") (pinfunction "62_62") (pintype "bidirectional"))
      (node (ref "X-SOUTH") (pin "64") (pinfunction "64_64") (pintype "bidirectional"))
    )
    (net (code "78") (name "OUT20_N") (class "Default")
      (node (ref "X-SOUTH") (pin "69") (pinfunction "69_69") (pintype "bidirectional"))
    )
    (net (code "79") (name "OUT20_P") (class "Default")
      (node (ref "X-SOUTH") (pin "67") (pinfunction "67_67") (pintype "bidirectional"))
    )
    (net (code "80") (name "OUT21_N") (class "Default")
      (node (ref "X-EAST") (pin "59") (pinfunction "59_59") (pintype "bidirectional"))
      (node (ref "X-SOUTH") (pin "63") (pinfunction "63_63") (pintype "bidirectional"))
    )
    (net (code "81") (name "OUT21_P") (class "Default")
      (node (ref "X-EAST") (pin "61") (pinfunction "61_61") (pintype "bidirectional"))
      (node (ref "X-SOUTH") (pin "61") (pinfunction "61_61") (pintype "bidirectional"))
    )
    (net (code "82") (name "OUT22_N") (class "Default")
      (node (ref "X-SOUTH") (pin "60") (pinfunction "60_60") (pintype "bidirectional"))
    )
    (net (code "83") (name "OUT22_P") (class "Default")
      (node (ref "X-SOUTH") (pin "58") (pinfunction "58_58") (pintype "bidirectional"))
    )
    (net (code "84") (name "OUT23_N") (class "Default")
      (node (ref "X-EAST") (pin "66") (pinfunction "66_66") (pintype "bidirectional"))
      (node (ref "X-SOUTH") (pin "54") (pinfunction "54_54") (pintype "bidirectional"))
    )
    (net (code "85") (name "OUT23_P") (class "Default")
      (node (ref "X-EAST") (pin "68") (pinfunction "68_68") (pintype "bidirectional"))
      (node (ref "X-SOUTH") (pin "52") (pinfunction "52_52") (pintype "bidirectional"))
    )
    (net (code "86") (name "OUT24_N") (class "Default")
      (node (ref "X-SOUTH") (pin "51") (pinfunction "51_51") (pintype "bidirectional"))
    )
    (net (code "87") (name "OUT24_P") (class "Default")
      (node (ref "X-SOUTH") (pin "49") (pinfunction "49_49") (pintype "bidirectional"))
    )
    (net (code "88") (name "OUT25_N") (class "Default")
      (node (ref "X-EAST") (pin "65") (pinfunction "65_65") (pintype "bidirectional"))
      (node (ref "X-SOUTH") (pin "57") (pinfunction "57_57") (pintype "bidirectional"))
    )
    (net (code "89") (name "OUT25_P") (class "Default")
      (node (ref "X-EAST") (pin "67") (pinfunction "67_67") (pintype "bidirectional"))
      (node (ref "X-SOUTH") (pin "55") (pinfunction "55_55") (pintype "bidirectional"))
    )
    (net (code "90") (name "OUT26_N") (class "Default")
      (node (ref "X-SOUTH") (pin "48") (pinfunction "48_48") (pintype "bidirectional"))
    )
    (net (code "91") (name "OUT26_P") (class "Default")
      (node (ref "X-SOUTH") (pin "46") (pinfunction "46_46") (pintype "bidirectional"))
    )
    (net (code "92") (name "OUT27_N") (class "Default")
      (node (ref "X-EAST") (pin "73") (pinfunction "73_73") (pintype "bidirectional"))
      (node (ref "X-SOUTH") (pin "39") (pinfunction "39_39") (pintype "bidirectional"))
    )
    (net (code "93") (name "OUT27_P") (class "Default")
      (node (ref "X-EAST") (pin "75") (pinfunction "75_75") (pintype "bidirectional"))
      (node (ref "X-SOUTH") (pin "37") (pinfunction "37_37") (pintype "bidirectional"))
    )
    (net (code "94") (name "OUT28_N") (class "Default")
      (node (ref "X-SOUTH") (pin "45") (pinfunction "45_45") (pintype "bidirectional"))
    )
    (net (code "95") (name "OUT28_P") (class "Default")
      (node (ref "X-SOUTH") (pin "43") (pinfunction "43_43") (pintype "bidirectional"))
    )
    (net (code "96") (name "OUT29_N") (class "Default")
      (node (ref "X-EAST") (pin "72") (pinfunction "72_72") (pintype "bidirectional"))
      (node (ref "X-SOUTH") (pin "42") (pinfunction "42_42") (pintype "bidirectional"))
    )
    (net (code "97") (name "OUT29_P") (class "Default")
      (node (ref "X-EAST") (pin "74") (pinfunction "74_74") (pintype "bidirectional"))
      (node (ref "X-SOUTH") (pin "40") (pinfunction "40_40") (pintype "bidirectional"))
    )
    (net (code "98") (name "OUT30_N") (class "Default")
      (node (ref "X-SOUTH") (pin "33") (pinfunction "33_33") (pintype "bidirectional"))
    )
    (net (code "99") (name "OUT30_P") (class "Default")
      (node (ref "X-SOUTH") (pin "31") (pinfunction "31_31") (pintype "bidirectional"))
    )
    (net (code "100") (name "OUT31_N") (class "Default")
      (node (ref "X-EAST") (pin "78") (pinfunction "78_78") (pintype "bidirectional"))
      (node (ref "X-SOUTH") (pin "36") (pinfunction "36_36") (pintype "bidirectional"))
    )
    (net (code "101") (name "OUT31_P") (class "Default")
      (node (ref "X-EAST") (pin "80") (pinfunction "80_80") (pintype "bidirectional"))
      (node (ref "X-SOUTH") (pin "34") (pinfunction "34_34") (pintype "bidirectional"))
    )
    (net (code "102") (name "OUT32_N") (class "Default")
      (node (ref "X-SOUTH") (pin "27") (pinfunction "27_27") (pintype "bidirectional"))
    )
    (net (code "103") (name "OUT32_P") (class "Default")
      (node (ref "X-SOUTH") (pin "25") (pinfunction "25_25") (pintype "bidirectional"))
    )
    (net (code "104") (name "OUT33_N") (class "Default")
      (node (ref "X-NORTH") (pin "19") (pinfunction "19_19") (pintype "bidirectional"))
      (node (ref "X-WEST") (pin "67") (pinfunction "67_67") (pintype "bidirectional"))
    )
    (net (code "105") (name "OUT33_P") (class "Default")
      (node (ref "X-NORTH") (pin "21") (pinfunction "21_21") (pintype "bidirectional"))
      (node (ref "X-WEST") (pin "65") (pinfunction "65_65") (pintype "bidirectional"))
    )
    (net (code "106") (name "OUT34_N") (class "Default")
      (node (ref "X-NORTH") (pin "28") (pinfunction "28_28") (pintype "bidirectional"))
    )
    (net (code "107") (name "OUT34_P") (class "Default")
      (node (ref "X-NORTH") (pin "30") (pinfunction "30_30") (pintype "bidirectional"))
    )
    (net (code "108") (name "OUT35_N") (class "Default")
      (node (ref "X-NORTH") (pin "25") (pinfunction "25_25") (pintype "bidirectional"))
      (node (ref "X-WEST") (pin "61") (pinfunction "61_61") (pintype "bidirectional"))
    )
    (net (code "109") (name "OUT35_P") (class "Default")
      (node (ref "X-NORTH") (pin "27") (pinfunction "27_27") (pintype "bidirectional"))
      (node (ref "X-WEST") (pin "59") (pinfunction "59_59") (pintype "bidirectional"))
    )
    (net (code "110") (name "OUT36_N") (class "Default")
      (node (ref "X-NORTH") (pin "34") (pinfunction "34_34") (pintype "bidirectional"))
    )
    (net (code "111") (name "OUT36_P") (class "Default")
      (node (ref "X-NORTH") (pin "36") (pinfunction "36_36") (pintype "bidirectional"))
    )
    (net (code "112") (name "OUT37_N") (class "Default")
      (node (ref "X-NORTH") (pin "31") (pinfunction "31_31") (pintype "bidirectional"))
      (node (ref "X-WEST") (pin "47") (pinfunction "47_47") (pintype "bidirectional"))
    )
    (net (code "113") (name "OUT37_P") (class "Default")
      (node (ref "X-NORTH") (pin "33") (pinfunction "33_33") (pintype "bidirectional"))
      (node (ref "X-WEST") (pin "45") (pinfunction "45_45") (pintype "bidirectional"))
    )
    (net (code "114") (name "OUT38_N") (class "Default")
      (node (ref "X-NORTH") (pin "37") (pinfunction "37_37") (pintype "bidirectional"))
    )
    (net (code "115") (name "OUT38_P") (class "Default")
      (node (ref "X-NORTH") (pin "39") (pinfunction "39_39") (pintype "bidirectional"))
    )
    (net (code "116") (name "OUT39_N") (class "Default")
      (node (ref "X-NORTH") (pin "40") (pinfunction "40_40") (pintype "bidirectional"))
      (node (ref "X-WEST") (pin "80") (pinfunction "80_80") (pintype "bidirectional"))
    )
    (net (code "117") (name "OUT39_P") (class "Default")
      (node (ref "X-NORTH") (pin "42") (pinfunction "42_42") (pintype "bidirectional"))
      (node (ref "X-WEST") (pin "78") (pinfunction "78_78") (pintype "bidirectional"))
    )
    (net (code "118") (name "OUT40_N") (class "Default")
      (node (ref "X-NORTH") (pin "43") (pinfunction "43_43") (pintype "bidirectional"))
    )
    (net (code "119") (name "OUT40_P") (class "Default")
      (node (ref "X-NORTH") (pin "45") (pinfunction "45_45") (pintype "bidirectional"))
    )
    (net (code "120") (name "OUT41_N") (class "Default")
      (node (ref "X-NORTH") (pin "46") (pinfunction "46_46") (pintype "bidirectional"))
      (node (ref "X-WEST") (pin "74") (pinfunction "74_74") (pintype "bidirectional"))
    )
    (net (code "121") (name "OUT41_P") (class "Default")
      (node (ref "X-NORTH") (pin "48") (pinfunction "48_48") (pintype "bidirectional"))
      (node (ref "X-WEST") (pin "72") (pinfunction "72_72") (pintype "bidirectional"))
    )
    (net (code "122") (name "OUT42_N") (class "Default")
      (node (ref "X-NORTH") (pin "49") (pinfunction "49_49") (pintype "bidirectional"))
    )
    (net (code "123") (name "OUT42_P") (class "Default")
      (node (ref "X-NORTH") (pin "51") (pinfunction "51_51") (pintype "bidirectional"))
    )
    (net (code "124") (name "OUT43_N") (class "Default")
      (node (ref "X-NORTH") (pin "52") (pinfunction "52_52") (pintype "bidirectional"))
      (node (ref "X-WEST") (pin "68") (pinfunction "68_68") (pintype "bidirectional"))
    )
    (net (code "125") (name "OUT43_P") (class "Default")
      (node (ref "X-NORTH") (pin "54") (pinfunction "54_54") (pintype "bidirectional"))
      (node (ref "X-WEST") (pin "66") (pinfunction "66_66") (pintype "bidirectional"))
    )
    (net (code "126") (name "OUT44_N") (class "Default")
      (node (ref "X-NORTH") (pin "55") (pinfunction "55_55") (pintype "bidirectional"))
    )
    (net (code "127") (name "OUT44_P") (class "Default")
      (node (ref "X-NORTH") (pin "57") (pinfunction "57_57") (pintype "bidirectional"))
    )
    (net (code "128") (name "OUT45_N") (class "Default")
      (node (ref "X-NORTH") (pin "58") (pinfunction "58_58") (pintype "bidirectional"))
      (node (ref "X-WEST") (pin "62") (pinfunction "62_62") (pintype "bidirectional"))
    )
    (net (code "129") (name "OUT45_P") (class "Default")
      (node (ref "X-NORTH") (pin "60") (pinfunction "60_60") (pintype "bidirectional"))
      (node (ref "X-WEST") (pin "60") (pinfunction "60_60") (pintype "bidirectional"))
    )
    (net (code "130") (name "OUT46_N") (class "Default")
      (node (ref "X-NORTH") (pin "61") (pinfunction "61_61") (pintype "bidirectional"))
    )
    (net (code "131") (name "OUT46_P") (class "Default")
      (node (ref "X-NORTH") (pin "63") (pinfunction "63_63") (pintype "bidirectional"))
    )
    (net (code "132") (name "OUT47_N") (class "Default")
      (node (ref "X-NORTH") (pin "64") (pinfunction "64_64") (pintype "bidirectional"))
      (node (ref "X-WEST") (pin "56") (pinfunction "56_56") (pintype "bidirectional"))
    )
    (net (code "133") (name "OUT47_P") (class "Default")
      (node (ref "X-NORTH") (pin "66") (pinfunction "66_66") (pintype "bidirectional"))
      (node (ref "X-WEST") (pin "54") (pinfunction "54_54") (pintype "bidirectional"))
    )
    (net (code "134") (name "OUT48_N") (class "Default")
      (node (ref "X-NORTH") (pin "67") (pinfunction "67_67") (pintype "bidirectional"))
    )
    (net (code "135") (name "OUT48_P") (class "Default")
      (node (ref "X-NORTH") (pin "69") (pinfunction "69_69") (pintype "bidirectional"))
    )
    (net (code "136") (name "OUT49_N") (class "Default")
      (node (ref "X-EAST") (pin "48") (pinfunction "48_48") (pintype "bidirectional"))
      (node (ref "X-NORTH") (pin "73") (pinfunction "73_73") (pintype "bidirectional"))
    )
    (net (code "137") (name "OUT49_P") (class "Default")
      (node (ref "X-EAST") (pin "46") (pinfunction "46_46") (pintype "bidirectional"))
      (node (ref "X-NORTH") (pin "75") (pinfunction "75_75") (pintype "bidirectional"))
    )
    (net (code "138") (name "OUT50_N") (class "Default")
      (node (ref "X-NORTH") (pin "70") (pinfunction "70_70") (pintype "bidirectional"))
    )
    (net (code "139") (name "OUT50_P") (class "Default")
      (node (ref "X-NORTH") (pin "72") (pinfunction "72_72") (pintype "bidirectional"))
    )
    (net (code "140") (name "OUT51_N") (class "Default")
      (node (ref "X-EAST") (pin "42") (pinfunction "42_42") (pintype "bidirectional"))
      (node (ref "X-NORTH") (pin "79") (pinfunction "79_79") (pintype "bidirectional"))
    )
    (net (code "141") (name "OUT51_P") (class "Default")
      (node (ref "X-EAST") (pin "40") (pinfunction "40_40") (pintype "bidirectional"))
      (node (ref "X-NORTH") (pin "81") (pinfunction "81_81") (pintype "bidirectional"))
    )
    (net (code "142") (name "OUT52_N") (class "Default")
      (node (ref "X-NORTH") (pin "76") (pinfunction "76_76") (pintype "bidirectional"))
    )
    (net (code "143") (name "OUT52_P") (class "Default")
      (node (ref "X-NORTH") (pin "78") (pinfunction "78_78") (pintype "bidirectional"))
    )
    (net (code "144") (name "OUT53_N") (class "Default")
      (node (ref "X-EAST") (pin "47") (pinfunction "47_47") (pintype "bidirectional"))
      (node (ref "X-NORTH") (pin "85") (pinfunction "85_85") (pintype "bidirectional"))
    )
    (net (code "145") (name "OUT53_P") (class "Default")
      (node (ref "X-EAST") (pin "45") (pinfunction "45_45") (pintype "bidirectional"))
      (node (ref "X-NORTH") (pin "87") (pinfunction "87_87") (pintype "bidirectional"))
    )
    (net (code "146") (name "OUT54_N") (class "Default")
      (node (ref "X-NORTH") (pin "82") (pinfunction "82_82") (pintype "bidirectional"))
    )
    (net (code "147") (name "OUT54_P") (class "Default")
      (node (ref "X-NORTH") (pin "84") (pinfunction "84_84") (pintype "bidirectional"))
    )
    (net (code "148") (name "OUT55_N") (class "Default")
      (node (ref "X-EAST") (pin "41") (pinfunction "41_41") (pintype "bidirectional"))
      (node (ref "X-NORTH") (pin "91") (pinfunction "91_91") (pintype "bidirectional"))
    )
    (net (code "149") (name "OUT55_P") (class "Default")
      (node (ref "X-EAST") (pin "39") (pinfunction "39_39") (pintype "bidirectional"))
      (node (ref "X-NORTH") (pin "93") (pinfunction "93_93") (pintype "bidirectional"))
    )
    (net (code "150") (name "OUT56_N") (class "Default")
      (node (ref "X-NORTH") (pin "88") (pinfunction "88_88") (pintype "bidirectional"))
    )
    (net (code "151") (name "OUT56_P") (class "Default")
      (node (ref "X-NORTH") (pin "90") (pinfunction "90_90") (pintype "bidirectional"))
    )
    (net (code "152") (name "OUT57_N") (class "Default")
      (node (ref "X-EAST") (pin "35") (pinfunction "35_35") (pintype "bidirectional"))
      (node (ref "X-NORTH") (pin "97") (pinfunction "97_97") (pintype "bidirectional"))
    )
    (net (code "153") (name "OUT57_P") (class "Default")
      (node (ref "X-EAST") (pin "33") (pinfunction "33_33") (pintype "bidirectional"))
      (node (ref "X-NORTH") (pin "99") (pinfunction "99_99") (pintype "bidirectional"))
    )
    (net (code "154") (name "OUT58_N") (class "Default")
      (node (ref "X-NORTH") (pin "94") (pinfunction "94_94") (pintype "bidirectional"))
    )
    (net (code "155") (name "OUT58_P") (class "Default")
      (node (ref "X-NORTH") (pin "96") (pinfunction "96_96") (pintype "bidirectional"))
    )
    (net (code "156") (name "OUT59_N") (class "Default")
      (node (ref "X-EAST") (pin "27") (pinfunction "27_27") (pintype "bidirectional"))
      (node (ref "X-NORTH") (pin "103") (pinfunction "103_103") (pintype "bidirectional"))
    )
    (net (code "157") (name "OUT59_P") (class "Default")
      (node (ref "X-EAST") (pin "25") (pinfunction "25_25") (pintype "bidirectional"))
      (node (ref "X-NORTH") (pin "105") (pinfunction "105_105") (pintype "bidirectional"))
    )
    (net (code "158") (name "OUT60_N") (class "Default")
      (node (ref "X-NORTH") (pin "109") (pinfunction "109_109") (pintype "bidirectional"))
    )
    (net (code "159") (name "OUT60_P") (class "Default")
      (node (ref "X-NORTH") (pin "111") (pinfunction "111_111") (pintype "bidirectional"))
    )
    (net (code "160") (name "OUT61_N") (class "Default")
      (node (ref "X-EAST") (pin "36") (pinfunction "36_36") (pintype "bidirectional"))
      (node (ref "X-NORTH") (pin "100") (pinfunction "100_100") (pintype "bidirectional"))
    )
    (net (code "161") (name "OUT61_P") (class "Default")
      (node (ref "X-EAST") (pin "34") (pinfunction "34_34") (pintype "bidirectional"))
      (node (ref "X-NORTH") (pin "102") (pinfunction "102_102") (pintype "bidirectional"))
    )
    (net (code "162") (name "OUT62_N") (class "Default")
      (node (ref "X-NORTH") (pin "115") (pinfunction "115_115") (pintype "bidirectional"))
    )
    (net (code "163") (name "OUT62_P") (class "Default")
      (node (ref "X-NORTH") (pin "117") (pinfunction "117_117") (pintype "bidirectional"))
    )
    (net (code "164") (name "OUT63_N") (class "Default")
      (node (ref "X-EAST") (pin "30") (pinfunction "30_30") (pintype "bidirectional"))
      (node (ref "X-NORTH") (pin "106") (pinfunction "106_106") (pintype "bidirectional"))
    )
    (net (code "165") (name "OUT63_P") (class "Default")
      (node (ref "X-EAST") (pin "28") (pinfunction "28_28") (pintype "bidirectional"))
      (node (ref "X-NORTH") (pin "108") (pinfunction "108_108") (pintype "bidirectional"))
    )
    (net (code "166") (name "OUT64_N") (class "Default")
      (node (ref "X-NORTH") (pin "112") (pinfunction "112_112") (pintype "bidirectional"))
    )
    (net (code "167") (name "OUT64_P") (class "Default")
      (node (ref "X-NORTH") (pin "114") (pinfunction "114_114") (pintype "bidirectional"))
    )
    (net (code "168") (name "OUTCLK_N") (class "Default")
      (node (ref "X-NORTH") (pin "16") (pinfunction "16_16") (pintype "bidirectional"))
      (node (ref "X-WEST") (pin "53") (pinfunction "53_53") (pintype "bidirectional"))
    )
    (net (code "169") (name "OUTCLK_P") (class "Default")
      (node (ref "X-NORTH") (pin "18") (pinfunction "18_18") (pintype "bidirectional"))
      (node (ref "X-WEST") (pin "55") (pinfunction "55_55") (pintype "bidirectional"))
    )
    (net (code "170") (name "OUTCTR_N") (class "Default")
      (node (ref "X-SOUTH") (pin "126") (pinfunction "126_126") (pintype "bidirectional"))
      (node (ref "X-WEST") (pin "22") (pinfunction "22_22") (pintype "bidirectional"))
    )
    (net (code "171") (name "OUTCTR_P") (class "Default")
      (node (ref "X-SOUTH") (pin "124") (pinfunction "124_124") (pintype "bidirectional"))
      (node (ref "X-WEST") (pin "24") (pinfunction "24_24") (pintype "bidirectional"))
    )
    (net (code "172") (name "S00_N") (class "Default")
      (node (ref "X-SOUTH") (pin "15") (pinfunction "15_15") (pintype "bidirectional"))
    )
    (net (code "173") (name "S00_P") (class "Default")
      (node (ref "X-SOUTH") (pin "13") (pinfunction "13_13") (pintype "bidirectional"))
    )
    (net (code "174") (name "S01_N") (class "Default")
      (node (ref "X-SOUTH") (pin "18") (pinfunction "18_18") (pintype "bidirectional"))
    )
    (net (code "175") (name "S01_P") (class "Default")
      (node (ref "X-SOUTH") (pin "16") (pinfunction "16_16") (pintype "bidirectional"))
    )
    (net (code "176") (name "S02_N") (class "Default")
      (node (ref "X-SOUTH") (pin "21") (pinfunction "21_21") (pintype "bidirectional"))
    )
    (net (code "177") (name "S02_P") (class "Default")
      (node (ref "X-SOUTH") (pin "19") (pinfunction "19_19") (pintype "bidirectional"))
    )
    (net (code "178") (name "S03_N") (class "Default")
      (node (ref "X-SOUTH") (pin "24") (pinfunction "24_24") (pintype "bidirectional"))
    )
    (net (code "179") (name "S03_P") (class "Default")
      (node (ref "X-SOUTH") (pin "22") (pinfunction "22_22") (pintype "bidirectional"))
    )
    (net (code "180") (name "S05_N") (class "Default")
      (node (ref "X-SOUTH") (pin "30") (pinfunction "30_30") (pintype "bidirectional"))
    )
    (net (code "181") (name "S05_P") (class "Default")
      (node (ref "X-SOUTH") (pin "28") (pinfunction "28_28") (pintype "bidirectional"))
    )
    (net (code "182") (name "S38_N") (class "Default")
      (node (ref "X-SOUTH") (pin "129") (pinfunction "129_129") (pintype "bidirectional"))
    )
    (net (code "183") (name "S38_P") (class "Default")
      (node (ref "X-SOUTH") (pin "127") (pinfunction "127_127") (pintype "bidirectional"))
    )
    (net (code "184") (name "S39_N") (class "Default")
      (node (ref "X-SOUTH") (pin "132") (pinfunction "132_132") (pintype "bidirectional"))
    )
    (net (code "185") (name "S39_P") (class "Default")
      (node (ref "X-SOUTH") (pin "130") (pinfunction "130_130") (pintype "bidirectional"))
    )
    (net (code "186") (name "SPI_EN") (class "Default")
      (node (ref "X-EAST") (pin "14") (pinfunction "14_14") (pintype "bidirectional"))
      (node (ref "X-NORTH") (pin "120") (pinfunction "120_120") (pintype "bidirectional"))
    )
    (net (code "187") (name "SYS_RES_N") (class "Default")
      (node (ref "X-EAST") (pin "22") (pinfunction "22_22") (pintype "bidirectional"))
      (node (ref "X-NORTH") (pin "126") (pinfunction "126_126") (pintype "bidirectional"))
    )
    (net (code "188") (name "S_CHK_V") (class "Default")
      (node (ref "X-EAST") (pin "92") (pinfunction "92_92") (pintype "bidirectional"))
      (node (ref "X-EAST") (pin "94") (pinfunction "94_94") (pintype "bidirectional"))
      (node (ref "X-SOUTH") (pin "7") (pinfunction "7_7") (pintype "bidirectional"))
      (node (ref "X-SOUTH") (pin "9") (pinfunction "9_9") (pintype "bidirectional"))
    )
    (net (code "189") (name "S_I2C_V") (class "Default")
      (node (ref "X-SOUTH") (pin "136") (pinfunction "136_136") (pintype "bidirectional"))
      (node (ref "X-SOUTH") (pin "138") (pinfunction "138_138") (pintype "bidirectional"))
      (node (ref "X-WEST") (pin "7") (pinfunction "7_7") (pintype "bidirectional"))
      (node (ref "X-WEST") (pin "9") (pinfunction "9_9") (pintype "bidirectional"))
    )
    (net (code "190") (name "S_SCK") (class "Default")
      (node (ref "X-SOUTH") (pin "143") (pinfunction "143_143") (pintype "bidirectional"))
      (node (ref "X-WEST") (pin "2") (pinfunction "2_2") (pintype "bidirectional"))
    )
    (net (code "191") (name "S_SCL") (class "Default")
      (node (ref "X-SOUTH") (pin "144") (pinfunction "144_144") (pintype "bidirectional"))
      (node (ref "X-WEST") (pin "1") (pinfunction "1_1") (pintype "bidirectional"))
    )
    (net (code "192") (name "S_SDA") (class "Default")
      (node (ref "X-SOUTH") (pin "142") (pinfunction "142_142") (pintype "bidirectional"))
      (node (ref "X-WEST") (pin "3") (pinfunction "3_3") (pintype "bidirectional"))
    )
    (net (code "193") (name "S_SDI") (class "Default")
      (node (ref "X-SOUTH") (pin "139") (pinfunction "139_139") (pintype "bidirectional"))
      (node (ref "X-WEST") (pin "6") (pinfunction "6_6") (pintype "bidirectional"))
    )
    (net (code "194") (name "S_SDO") (class "Default")
      (node (ref "X-SOUTH") (pin "141") (pinfunction "141_141") (pintype "bidirectional"))
      (node (ref "X-WEST") (pin "4") (pinfunction "4_4") (pintype "bidirectional"))
    )
    (net (code "195") (name "S_SPI_V") (class "Default")
      (node (ref "X-SOUTH") (pin "133") (pinfunction "133_133") (pintype "bidirectional"))
      (node (ref "X-SOUTH") (pin "135") (pinfunction "135_135") (pintype "bidirectional"))
      (node (ref "X-WEST") (pin "10") (pinfunction "10_10") (pintype "bidirectional"))
      (node (ref "X-WEST") (pin "8") (pinfunction "8_8") (pintype "bidirectional"))
    )
    (net (code "196") (name "S_VE") (class "Default")
      (node (ref "C7") (pin "1") (pinfunction "1_1") (pintype "passive"))
      (node (ref "P-E") (pin "5") (pinfunction "5_5") (pintype "passive"))
      (node (ref "X-EAST") (pin "51") (pinfunction "51_51") (pintype "bidirectional"))
      (node (ref "X-EAST") (pin "57") (pinfunction "57_57") (pintype "bidirectional"))
      (node (ref "X-EAST") (pin "63") (pinfunction "63_63") (pintype "bidirectional"))
      (node (ref "X-EAST") (pin "69") (pinfunction "69_69") (pintype "bidirectional"))
      (node (ref "X-SOUTH") (pin "14") (pinfunction "14_14") (pintype "bidirectional"))
      (node (ref "X-SOUTH") (pin "20") (pinfunction "20_20") (pintype "bidirectional"))
      (node (ref "X-SOUTH") (pin "26") (pinfunction "26_26") (pintype "bidirectional"))
      (node (ref "X-SOUTH") (pin "32") (pinfunction "32_32") (pintype "bidirectional"))
      (node (ref "X-SOUTH") (pin "38") (pinfunction "38_38") (pintype "bidirectional"))
    )
    (net (code "197") (name "S_VE_CV") (class "Default")
      (node (ref "X-EAST") (pin "100") (pinfunction "100_100") (pintype "bidirectional"))
      (node (ref "X-SOUTH") (pin "1") (pinfunction "1_1") (pintype "bidirectional"))
    )
    (net (code "198") (name "S_VE_OV") (class "Default")
      (node (ref "X-EAST") (pin "99") (pinfunction "99_99") (pintype "bidirectional"))
      (node (ref "X-SOUTH") (pin "2") (pinfunction "2_2") (pintype "bidirectional"))
    )
    (net (code "199") (name "S_VE_UV") (class "Default")
      (node (ref "X-EAST") (pin "89") (pinfunction "89_89") (pintype "bidirectional"))
      (node (ref "X-SOUTH") (pin "8") (pinfunction "8_8") (pintype "bidirectional"))
    )
    (net (code "200") (name "S_VS") (class "Default")
      (node (ref "C6") (pin "1") (pinfunction "1_1") (pintype "passive"))
      (node (ref "P-E") (pin "3") (pinfunction "3_3") (pintype "passive"))
      (node (ref "X-EAST") (pin "32") (pinfunction "32_32") (pintype "bidirectional"))
      (node (ref "X-EAST") (pin "38") (pinfunction "38_38") (pintype "bidirectional"))
      (node (ref "X-EAST") (pin "44") (pinfunction "44_44") (pintype "bidirectional"))
      (node (ref "X-EAST") (pin "50") (pinfunction "50_50") (pintype "bidirectional"))
      (node (ref "X-EAST") (pin "52") (pinfunction "52_52") (pintype "bidirectional"))
      (node (ref "X-EAST") (pin "58") (pinfunction "58_58") (pintype "bidirectional"))
      (node (ref "X-EAST") (pin "64") (pinfunction "64_64") (pintype "bidirectional"))
      (node (ref "X-EAST") (pin "70") (pinfunction "70_70") (pintype "bidirectional"))
      (node (ref "X-SOUTH") (pin "50") (pinfunction "50_50") (pintype "bidirectional"))
      (node (ref "X-SOUTH") (pin "56") (pinfunction "56_56") (pintype "bidirectional"))
      (node (ref "X-SOUTH") (pin "62") (pinfunction "62_62") (pintype "bidirectional"))
      (node (ref "X-SOUTH") (pin "68") (pinfunction "68_68") (pintype "bidirectional"))
      (node (ref "X-SOUTH") (pin "74") (pinfunction "74_74") (pintype "bidirectional"))
      (node (ref "X-SOUTH") (pin "80") (pinfunction "80_80") (pintype "bidirectional"))
      (node (ref "X-SOUTH") (pin "86") (pinfunction "86_86") (pintype "bidirectional"))
      (node (ref "X-SOUTH") (pin "92") (pinfunction "92_92") (pintype "bidirectional"))
      (node (ref "X-SOUTH") (pin "98") (pinfunction "98_98") (pintype "bidirectional"))
    )
    (net (code "201") (name "S_VS_CV") (class "Default")
      (node (ref "X-EAST") (pin "98") (pinfunction "98_98") (pintype "bidirectional"))
      (node (ref "X-SOUTH") (pin "3") (pinfunction "3_3") (pintype "bidirectional"))
    )
    (net (code "202") (name "S_VS_OV") (class "Default")
      (node (ref "X-EAST") (pin "97") (pinfunction "97_97") (pintype "bidirectional"))
      (node (ref "X-SOUTH") (pin "4") (pinfunction "4_4") (pintype "bidirectional"))
    )
    (net (code "203") (name "S_VS_UV") (class "Default")
      (node (ref "X-EAST") (pin "87") (pinfunction "87_87") (pintype "bidirectional"))
      (node (ref "X-SOUTH") (pin "10") (pinfunction "10_10") (pintype "bidirectional"))
    )
    (net (code "204") (name "S_VW") (class "Default")
      (node (ref "C2") (pin "1") (pinfunction "1_1") (pintype "passive"))
      (node (ref "P-W") (pin "1") (pinfunction "1_1") (pintype "passive"))
      (node (ref "X-SOUTH") (pin "110") (pinfunction "110_110") (pintype "bidirectional"))
      (node (ref "X-SOUTH") (pin "116") (pinfunction "116_116") (pintype "bidirectional"))
      (node (ref "X-SOUTH") (pin "122") (pinfunction "122_122") (pintype "bidirectional"))
      (node (ref "X-SOUTH") (pin "128") (pinfunction "128_128") (pintype "bidirectional"))
      (node (ref "X-SOUTH") (pin "134") (pinfunction "134_134") (pintype "bidirectional"))
      (node (ref "X-WEST") (pin "31") (pinfunction "31_31") (pintype "bidirectional"))
      (node (ref "X-WEST") (pin "37") (pinfunction "37_37") (pintype "bidirectional"))
      (node (ref "X-WEST") (pin "43") (pinfunction "43_43") (pintype "bidirectional"))
      (node (ref "X-WEST") (pin "49") (pinfunction "49_49") (pintype "bidirectional"))
    )
    (net (code "205") (name "S_VW_CV") (class "Default")
      (node (ref "X-EAST") (pin "96") (pinfunction "96_96") (pintype "bidirectional"))
      (node (ref "X-SOUTH") (pin "5") (pinfunction "5_5") (pintype "bidirectional"))
    )
    (net (code "206") (name "S_VW_OV") (class "Default")
      (node (ref "X-EAST") (pin "95") (pinfunction "95_95") (pintype "bidirectional"))
      (node (ref "X-SOUTH") (pin "6") (pinfunction "6_6") (pintype "bidirectional"))
    )
    (net (code "207") (name "S_VW_UV") (class "Default")
      (node (ref "X-EAST") (pin "85") (pinfunction "85_85") (pintype "bidirectional"))
      (node (ref "X-SOUTH") (pin "12") (pinfunction "12_12") (pintype "bidirectional"))
    )
    (net (code "208") (name "TCK") (class "Default")
      (node (ref "X-WEST") (pin "12") (pinfunction "12_12") (pintype "bidirectional"))
    )
    (net (code "209") (name "TDI") (class "Default")
      (node (ref "X-WEST") (pin "16") (pinfunction "16_16") (pintype "bidirectional"))
    )
    (net (code "210") (name "TDIG1") (class "Default")
      (node (ref "X-EAST") (pin "18") (pinfunction "18_18") (pintype "bidirectional"))
      (node (ref "X-NORTH") (pin "124") (pinfunction "124_124") (pintype "bidirectional"))
    )
    (net (code "211") (name "TDIG2") (class "Default")
      (node (ref "X-EAST") (pin "17") (pinfunction "17_17") (pintype "bidirectional"))
      (node (ref "X-NORTH") (pin "129") (pinfunction "129_129") (pintype "bidirectional"))
    )
    (net (code "212") (name "TDO") (class "Default")
      (node (ref "X-WEST") (pin "18") (pinfunction "18_18") (pintype "bidirectional"))
    )
    (net (code "213") (name "TMS") (class "Default")
      (node (ref "X-WEST") (pin "14") (pinfunction "14_14") (pintype "bidirectional"))
    )
    (net (code "214") (name "T_EXP1") (class "Default")
      (node (ref "X-EAST") (pin "12") (pinfunction "12_12") (pintype "bidirectional"))
      (node (ref "X-NORTH") (pin "132") (pinfunction "132_132") (pintype "bidirectional"))
    )
    (net (code "215") (name "T_EXP2") (class "Default")
      (node (ref "X-EAST") (pin "16") (pinfunction "16_16") (pintype "bidirectional"))
      (node (ref "X-NORTH") (pin "118") (pinfunction "118_118") (pintype "bidirectional"))
    )
    (net (code "216") (name "W_I2C_V") (class "Default")
      (node (ref "X-WEST") (pin "11") (pinfunction "11_11") (pintype "bidirectional"))
      (node (ref "X-WEST") (pin "13") (pinfunction "13_13") (pintype "bidirectional"))
    )
    (net (code "217") (name "W_SCL") (class "Default")
      (node (ref "X-WEST") (pin "15") (pinfunction "15_15") (pintype "bidirectional"))
    )
    (net (code "218") (name "W_SDA") (class "Default")
      (node (ref "X-WEST") (pin "17") (pinfunction "17_17") (pintype "bidirectional"))
    )
    (net (code "219") (name "W_VW") (class "Default")
      (node (ref "X-WEST") (pin "79") (pinfunction "79_79") (pintype "bidirectional"))
      (node (ref "X-WEST") (pin "81") (pinfunction "81_81") (pintype "bidirectional"))
      (node (ref "X-WEST") (pin "83") (pinfunction "83_83") (pintype "bidirectional"))
      (node (ref "X-WEST") (pin "84") (pinfunction "84_84") (pintype "bidirectional"))
      (node (ref "X-WEST") (pin "86") (pinfunction "86_86") (pintype "bidirectional"))
      (node (ref "X-WEST") (pin "88") (pinfunction "88_88") (pintype "bidirectional"))
    )
    (net (code "220") (name "W_VW_CV") (class "Default")
      (node (ref "X-WEST") (pin "90") (pinfunction "90_90") (pintype "bidirectional"))
    )
    (net (code "221") (name "W_VW_OV") (class "Default")
      (node (ref "X-WEST") (pin "93") (pinfunction "93_93") (pintype "bidirectional"))
    )
    (net (code "222") (name "W_VW_UV") (class "Default")
      (node (ref "X-WEST") (pin "91") (pinfunction "91_91") (pintype "bidirectional"))
    )
    (net (code "223") (name "unconnected-(X-EAST-PadM1)") (class "Default")
      (node (ref "X-EAST") (pin "M1") (pinfunction "M1_M1") (pintype "bidirectional"))
    )
    (net (code "224") (name "unconnected-(X-EAST-PadM2)") (class "Default")
      (node (ref "X-EAST") (pin "M2") (pinfunction "M2_M2") (pintype "bidirectional"))
    )
    (net (code "225") (name "unconnected-(X-NORTH-PadM1)") (class "Default")
      (node (ref "X-NORTH") (pin "M1") (pinfunction "M1_M1") (pintype "bidirectional"))
    )
    (net (code "226") (name "unconnected-(X-NORTH-PadM2)") (class "Default")
      (node (ref "X-NORTH") (pin "M2") (pinfunction "M2_M2") (pintype "bidirectional"))
    )
    (net (code "227") (name "unconnected-(X-SOUTH-PadM1)") (class "Default")
      (node (ref "X-SOUTH") (pin "M1") (pinfunction "M1_M1") (pintype "bidirectional"))
    )
    (net (code "228") (name "unconnected-(X-SOUTH-PadM2)") (class "Default")
      (node (ref "X-SOUTH") (pin "M2") (pinfunction "M2_M2") (pintype "bidirectional"))
    )
    (net (code "229") (name "unconnected-(X-WEST-PadM1)") (class "Default")
      (node (ref "X-WEST") (pin "M1") (pinfunction "M1_M1") (pintype "bidirectional"))
    )
    (net (code "230") (name "unconnected-(X-WEST-PadM2)") (class "Default")
      (node (ref "X-WEST") (pin "M2") (pinfunction "M2_M2") (pintype "bidirectional"))
    )
  )
)
